# Schematic_v2.net
KiCad netlist of a schematic drawn in EAGLE
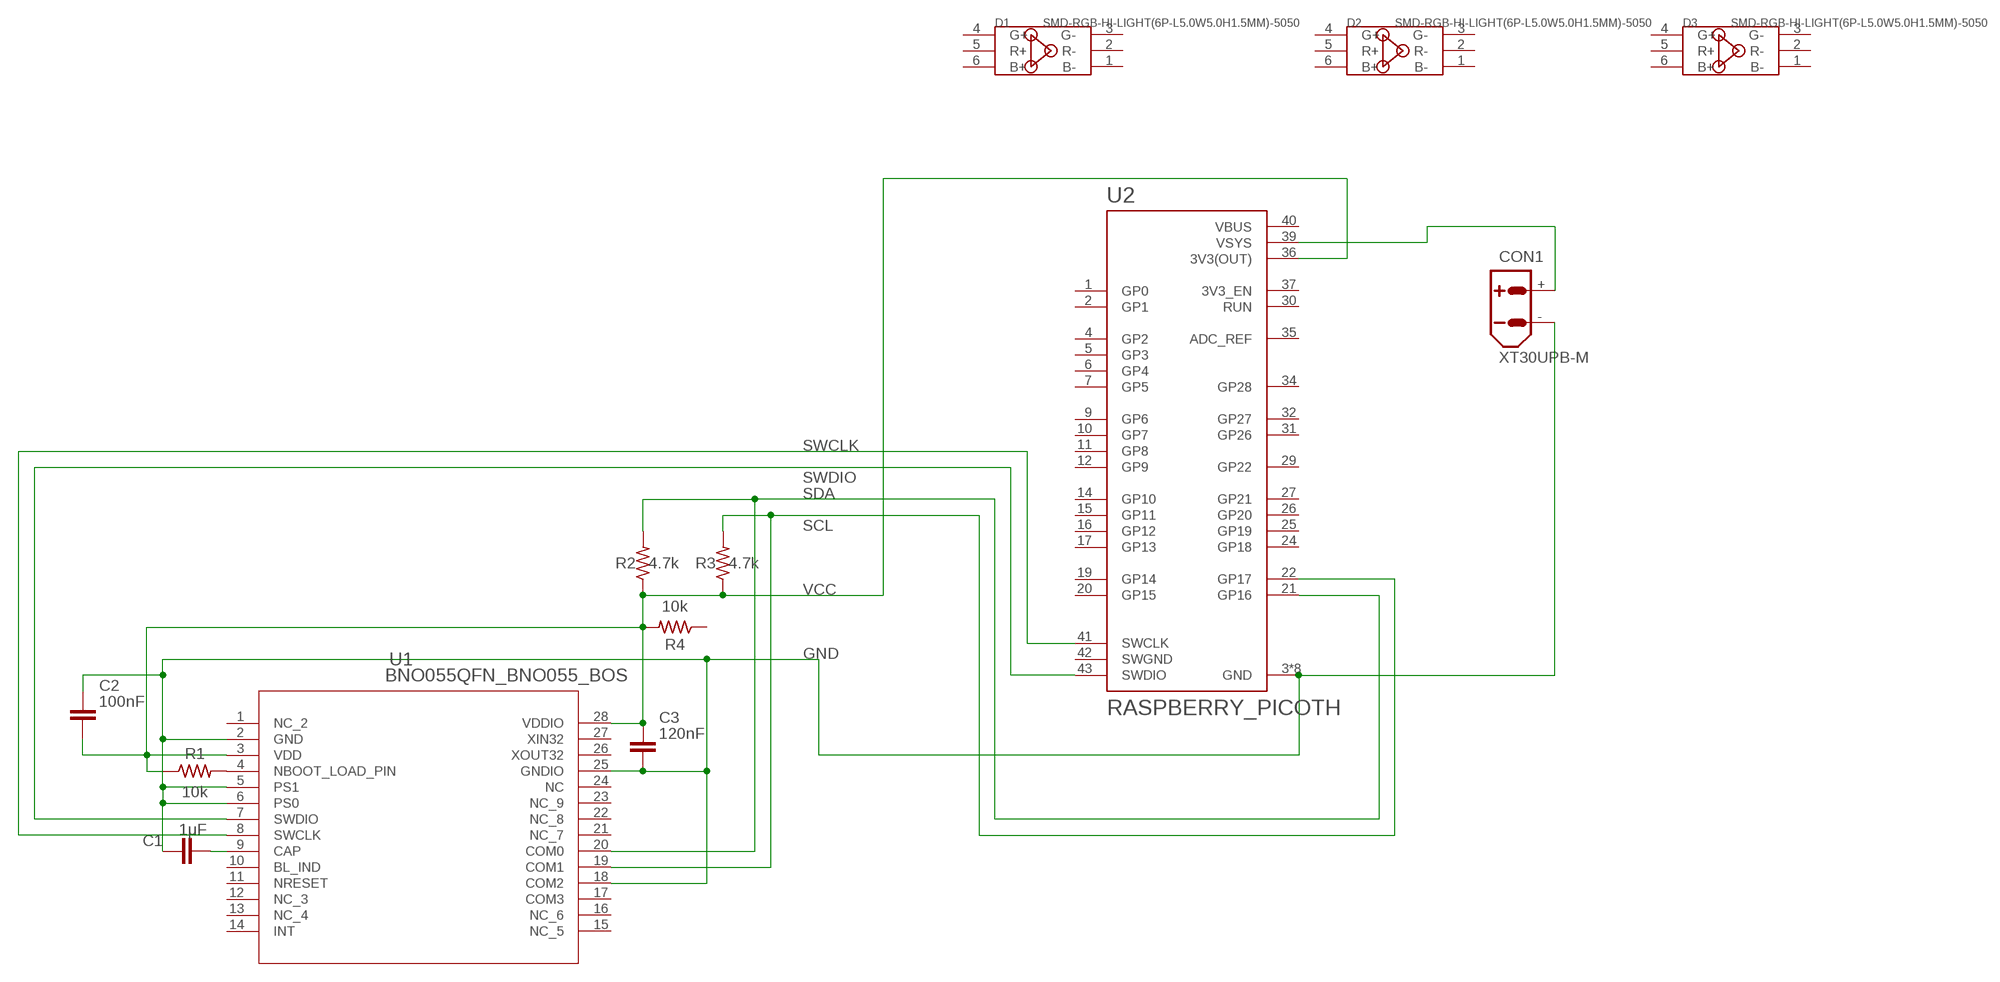
[diagram p0: schematic, sheet 1]

(export (version "E")
  (design (tool "Eeschema 10.0.6"))
  (components
    (comp (ref "C1")
      (value "1μF")
      (footprint "eagle-import:CAPC3216X135")
      (libsource (lib "eagle-import") (part "CCHIP-1206(3216-METRIC)_"))
    )
    (comp (ref "C2")
      (value "100nF")
      (footprint "eagle-import:CAPC3216X135")
      (libsource (lib "eagle-import") (part "CCHIP-1206(3216-METRIC)_"))
    )
    (comp (ref "C3")
      (value "120nF")
      (footprint "eagle-import:CAPC3216X135")
      (libsource (lib "eagle-import") (part "CCHIP-1206(3216-METRIC)_"))
    )
    (comp (ref "CON1")
      (value "XT30UPB-M")
      (footprint "eagle-import:XT30UPB-M")
      (libsource (lib "eagle-import") (part "XT30UPB-M"))
    )
    (comp (ref "D1")
      (value "SMD-RGB-HI-LIGHT(6P-L5.0W5.0H1.5MM)-5050")
      (footprint "eagle-import:LED6-SMD-5050")
      (fields (field (name "MF") "SparkFun Electronics") (field (name "MP") "5050RGB"))
      (libsource (lib "eagle-import") (part "SMD-RGB-HI-LIGHT(6P-L5.0W5.0H1.5MM)-5050"))
    )
    (comp (ref "D2")
      (value "SMD-RGB-HI-LIGHT(6P-L5.0W5.0H1.5MM)-5050")
      (footprint "eagle-import:LED6-SMD-5050")
      (fields (field (name "MF") "SparkFun Electronics") (field (name "MP") "5050RGB"))
      (libsource (lib "eagle-import") (part "SMD-RGB-HI-LIGHT(6P-L5.0W5.0H1.5MM)-5050"))
    )
    (comp (ref "D3")
      (value "SMD-RGB-HI-LIGHT(6P-L5.0W5.0H1.5MM)-5050")
      (footprint "eagle-import:LED6-SMD-5050")
      (fields (field (name "MF") "SparkFun Electronics") (field (name "MP") "5050RGB"))
      (libsource (lib "eagle-import") (part "SMD-RGB-HI-LIGHT(6P-L5.0W5.0H1.5MM)-5050"))
    )
    (comp (ref "R1")
      (value "10k")
      (footprint "eagle-import:RESC3216X70")
      (libsource (lib "eagle-import") (part "R-USCHIP-1206(3216-METRIC)_"))
    )
    (comp (ref "R2")
      (value "4.7k")
      (footprint "eagle-import:RESC3216X70")
      (libsource (lib "eagle-import") (part "R-USCHIP-1206(3216-METRIC)_"))
    )
    (comp (ref "R3")
      (value "4.7k")
      (footprint "eagle-import:RESC3216X70")
      (libsource (lib "eagle-import") (part "R-USCHIP-1206(3216-METRIC)_"))
    )
    (comp (ref "R4")
      (value "10k")
      (footprint "eagle-import:RESC3216X70")
      (libsource (lib "eagle-import") (part "R-USCHIP-1206(3216-METRIC)_"))
    )
    (comp (ref "U1")
      (value "BNO055QFN_BNO055_BOS")
      (footprint "eagle-import:QFN_BNO055_BOS")
      (fields
        (field (name "MANUFACTURER_PART_NUMBER") "BNO055")
        (field (name "COPYRIGHT") "Copyright (C) 2024 Ultra Librarian. All rights reserved.")
      )
      (libsource (lib "eagle-import") (part "BNO055QFN_BNO055_BOS"))
    )
    (comp (ref "U2")
      (value "RASPBERRY_PICOTH")
      (footprint "eagle-import:PICO-PKG-TH")
      (libsource (lib "eagle-import") (part "RASPBERRY_PICOTH"))
    )
  )
  (nets
    (net (code "1") (name "/GND") (class "Default")
      (node (ref "C1") (pin "1") (pinfunction "1_1") (pintype "passive"))
      (node (ref "C2") (pin "1") (pinfunction "1_1") (pintype "passive"))
      (node (ref "C3") (pin "2") (pinfunction "2_2") (pintype "passive"))
      (node (ref "CON1") (pin "-") (pinfunction "-_-") (pintype "power_in"))
      (node (ref "U1") (pin "18") (pinfunction "COM2_18") (pintype "bidirectional"))
      (node (ref "U1") (pin "2") (pinfunction "GND_2") (pintype "passive"))
      (node (ref "U1") (pin "25") (pinfunction "GNDIO_25") (pintype "passive"))
      (node (ref "U1") (pin "5") (pinfunction "PS1_5") (pintype "input"))
      (node (ref "U1") (pin "6") (pinfunction "PS0_6") (pintype "input"))
      (node (ref "U2") (pin "13") (pinfunction "GND_13") (pintype "power_in"))
      (node (ref "U2") (pin "18") (pinfunction "GND_18") (pintype "power_in"))
      (node (ref "U2") (pin "23") (pinfunction "GND_23") (pintype "power_in"))
      (node (ref "U2") (pin "28") (pinfunction "GND_28") (pintype "power_in"))
      (node (ref "U2") (pin "3") (pinfunction "GND_3") (pintype "power_in"))
      (node (ref "U2") (pin "33") (pinfunction "GND_33") (pintype "power_in"))
      (node (ref "U2") (pin "38") (pinfunction "GND_38") (pintype "power_in"))
      (node (ref "U2") (pin "8") (pinfunction "GND_8") (pintype "power_in"))
    )
    (net (code "2") (name "/SCL") (class "Default")
      (node (ref "R3") (pin "2") (pinfunction "2_2") (pintype "passive"))
      (node (ref "U1") (pin "19") (pinfunction "COM1_19") (pintype "bidirectional"))
      (node (ref "U2") (pin "22") (pinfunction "GP17_22") (pintype "bidirectional"))
    )
    (net (code "3") (name "/SDA") (class "Default")
      (node (ref "R2") (pin "2") (pinfunction "2_2") (pintype "passive"))
      (node (ref "U1") (pin "20") (pinfunction "COM0_20") (pintype "bidirectional"))
      (node (ref "U2") (pin "21") (pinfunction "GP16_21") (pintype "bidirectional"))
    )
    (net (code "4") (name "/SWCLK") (class "Default")
      (node (ref "U1") (pin "8") (pinfunction "SWCLK_8") (pintype "input"))
      (node (ref "U2") (pin "41") (pinfunction "SWCLK_41") (pintype "input"))
    )
    (net (code "5") (name "/SWDIO") (class "Default")
      (node (ref "U1") (pin "7") (pinfunction "SWDIO_7") (pintype "bidirectional"))
      (node (ref "U2") (pin "43") (pinfunction "SWDIO_43") (pintype "bidirectional"))
    )
    (net (code "6") (name "/SWGND") (class "Default")
      (node (ref "U2") (pin "42") (pinfunction "SWGND_42") (pintype "power_in"))
    )
    (net (code "7") (name "/VBUS") (class "Default")
      (node (ref "U2") (pin "40") (pinfunction "VBUS_40") (pintype "power_in"))
    )
    (net (code "8") (name "/VCC") (class "Default")
      (node (ref "C2") (pin "2") (pinfunction "2_2") (pintype "passive"))
      (node (ref "C3") (pin "1") (pinfunction "1_1") (pintype "passive"))
      (node (ref "R1") (pin "1") (pinfunction "1_1") (pintype "passive"))
      (node (ref "R2") (pin "1") (pinfunction "1_1") (pintype "passive"))
      (node (ref "R3") (pin "1") (pinfunction "1_1") (pintype "passive"))
      (node (ref "R4") (pin "2") (pinfunction "2_2") (pintype "passive"))
      (node (ref "U1") (pin "28") (pinfunction "VDDIO_28") (pintype "power_in"))
      (node (ref "U1") (pin "3") (pinfunction "VDD_3") (pintype "power_in"))
      (node (ref "U2") (pin "36") (pinfunction "3V3(OUT)_36") (pintype "power_in"))
    )
    (net (code "9") (name "Net-(U1-CAP)") (class "Default")
      (node (ref "C1") (pin "2") (pinfunction "2_2") (pintype "passive"))
      (node (ref "U1") (pin "9") (pinfunction "CAP_9") (pintype "passive"))
    )
    (net (code "10") (name "Net-(U1-NBOOT_LOAD_PIN)") (class "Default")
      (node (ref "R1") (pin "2") (pinfunction "2_2") (pintype "passive"))
      (node (ref "U1") (pin "4") (pinfunction "NBOOT_LOAD_PIN_4") (pintype "input"))
    )
    (net (code "11") (name "Net-(U2-VSYS)") (class "Default")
      (node (ref "CON1") (pin "+") (pinfunction "+_+") (pintype "power_in"))
      (node (ref "U2") (pin "39") (pinfunction "VSYS_39") (pintype "power_in"))
    )
    (net (code "12") (name "unconnected-(D1-B+-Pad6)") (class "Default")
      (node (ref "D1") (pin "6") (pinfunction "B+_6") (pintype "bidirectional"))
    )
    (net (code "13") (name "unconnected-(D1-B--Pad1)") (class "Default")
      (node (ref "D1") (pin "1") (pinfunction "B-_1") (pintype "bidirectional"))
    )
    (net (code "14") (name "unconnected-(D1-G+-Pad4)") (class "Default")
      (node (ref "D1") (pin "4") (pinfunction "G+_4") (pintype "bidirectional"))
    )
    (net (code "15") (name "unconnected-(D1-G--Pad3)") (class "Default")
      (node (ref "D1") (pin "3") (pinfunction "G-_3") (pintype "bidirectional"))
    )
    (net (code "16") (name "unconnected-(D1-R+-Pad5)") (class "Default")
      (node (ref "D1") (pin "5") (pinfunction "R+_5") (pintype "bidirectional"))
    )
    (net (code "17") (name "unconnected-(D1-R--Pad2)") (class "Default")
      (node (ref "D1") (pin "2") (pinfunction "R-_2") (pintype "bidirectional"))
    )
    (net (code "18") (name "unconnected-(D2-B+-Pad6)") (class "Default")
      (node (ref "D2") (pin "6") (pinfunction "B+_6") (pintype "bidirectional"))
    )
    (net (code "19") (name "unconnected-(D2-B--Pad1)") (class "Default")
      (node (ref "D2") (pin "1") (pinfunction "B-_1") (pintype "bidirectional"))
    )
    (net (code "20") (name "unconnected-(D2-G+-Pad4)") (class "Default")
      (node (ref "D2") (pin "4") (pinfunction "G+_4") (pintype "bidirectional"))
    )
    (net (code "21") (name "unconnected-(D2-G--Pad3)") (class "Default")
      (node (ref "D2") (pin "3") (pinfunction "G-_3") (pintype "bidirectional"))
    )
    (net (code "22") (name "unconnected-(D2-R+-Pad5)") (class "Default")
      (node (ref "D2") (pin "5") (pinfunction "R+_5") (pintype "bidirectional"))
    )
    (net (code "23") (name "unconnected-(D2-R--Pad2)") (class "Default")
      (node (ref "D2") (pin "2") (pinfunction "R-_2") (pintype "bidirectional"))
    )
    (net (code "24") (name "unconnected-(D3-B+-Pad6)") (class "Default")
      (node (ref "D3") (pin "6") (pinfunction "B+_6") (pintype "bidirectional"))
    )
    (net (code "25") (name "unconnected-(D3-B--Pad1)") (class "Default")
      (node (ref "D3") (pin "1") (pinfunction "B-_1") (pintype "bidirectional"))
    )
    (net (code "26") (name "unconnected-(D3-G+-Pad4)") (class "Default")
      (node (ref "D3") (pin "4") (pinfunction "G+_4") (pintype "bidirectional"))
    )
    (net (code "27") (name "unconnected-(D3-G--Pad3)") (class "Default")
      (node (ref "D3") (pin "3") (pinfunction "G-_3") (pintype "bidirectional"))
    )
    (net (code "28") (name "unconnected-(D3-R+-Pad5)") (class "Default")
      (node (ref "D3") (pin "5") (pinfunction "R+_5") (pintype "bidirectional"))
    )
    (net (code "29") (name "unconnected-(D3-R--Pad2)") (class "Default")
      (node (ref "D3") (pin "2") (pinfunction "R-_2") (pintype "bidirectional"))
    )
    (net (code "30") (name "unconnected-(R4-Pad1)") (class "Default")
      (node (ref "R4") (pin "1") (pinfunction "1_1") (pintype "passive"))
    )
    (net (code "31") (name "unconnected-(U1-BL_IND-Pad10)") (class "Default")
      (node (ref "U1") (pin "10") (pinfunction "BL_IND_10") (pintype "output"))
    )
    (net (code "32") (name "unconnected-(U1-COM3-Pad17)") (class "Default")
      (node (ref "U1") (pin "17") (pinfunction "COM3_17") (pintype "input"))
    )
    (net (code "33") (name "unconnected-(U1-INT-Pad14)") (class "Default")
      (node (ref "U1") (pin "14") (pinfunction "INT_14") (pintype "output"))
    )
    (net (code "34") (name "unconnected-(U1-NC-Pad24)") (class "Default")
      (node (ref "U1") (pin "24") (pinfunction "NC_24") (pintype "no_connect"))
    )
    (net (code "35") (name "unconnected-(U1-NC_2-Pad1)") (class "Default")
      (node (ref "U1") (pin "1") (pinfunction "NC_2_1") (pintype "no_connect"))
    )
    (net (code "36") (name "unconnected-(U1-NC_3-Pad12)") (class "Default")
      (node (ref "U1") (pin "12") (pinfunction "NC_3_12") (pintype "no_connect"))
    )
    (net (code "37") (name "unconnected-(U1-NC_4-Pad13)") (class "Default")
      (node (ref "U1") (pin "13") (pinfunction "NC_4_13") (pintype "no_connect"))
    )
    (net (code "38") (name "unconnected-(U1-NC_5-Pad15)") (class "Default")
      (node (ref "U1") (pin "15") (pinfunction "NC_5_15") (pintype "no_connect"))
    )
    (net (code "39") (name "unconnected-(U1-NC_6-Pad16)") (class "Default")
      (node (ref "U1") (pin "16") (pinfunction "NC_6_16") (pintype "no_connect"))
    )
    (net (code "40") (name "unconnected-(U1-NC_7-Pad21)") (class "Default")
      (node (ref "U1") (pin "21") (pinfunction "NC_7_21") (pintype "no_connect"))
    )
    (net (code "41") (name "unconnected-(U1-NC_8-Pad22)") (class "Default")
      (node (ref "U1") (pin "22") (pinfunction "NC_8_22") (pintype "no_connect"))
    )
    (net (code "42") (name "unconnected-(U1-NC_9-Pad23)") (class "Default")
      (node (ref "U1") (pin "23") (pinfunction "NC_9_23") (pintype "no_connect"))
    )
    (net (code "43") (name "unconnected-(U1-NRESET-Pad11)") (class "Default")
      (node (ref "U1") (pin "11") (pinfunction "NRESET_11") (pintype "passive"))
    )
    (net (code "44") (name "unconnected-(U1-XIN32-Pad27)") (class "Default")
      (node (ref "U1") (pin "27") (pinfunction "XIN32_27") (pintype "input"))
    )
    (net (code "45") (name "unconnected-(U1-XOUT32-Pad26)") (class "Default")
      (node (ref "U1") (pin "26") (pinfunction "XOUT32_26") (pintype "output"))
    )
    (net (code "46") (name "unconnected-(U2-3V3_EN-Pad37)") (class "Default")
      (node (ref "U2") (pin "37") (pinfunction "3V3_EN_37") (pintype "input"))
    )
    (net (code "47") (name "unconnected-(U2-ADC_REF-Pad35)") (class "Default")
      (node (ref "U2") (pin "35") (pinfunction "ADC_REF_35") (pintype "input"))
    )
    (net (code "48") (name "unconnected-(U2-GP0-Pad1)") (class "Default")
      (node (ref "U2") (pin "1") (pinfunction "GP0_1") (pintype "bidirectional"))
    )
    (net (code "49") (name "unconnected-(U2-GP1-Pad2)") (class "Default")
      (node (ref "U2") (pin "2") (pinfunction "GP1_2") (pintype "bidirectional"))
    )
    (net (code "50") (name "unconnected-(U2-GP2-Pad4)") (class "Default")
      (node (ref "U2") (pin "4") (pinfunction "GP2_4") (pintype "bidirectional"))
    )
    (net (code "51") (name "unconnected-(U2-GP3-Pad5)") (class "Default")
      (node (ref "U2") (pin "5") (pinfunction "GP3_5") (pintype "bidirectional"))
    )
    (net (code "52") (name "unconnected-(U2-GP4-Pad6)") (class "Default")
      (node (ref "U2") (pin "6") (pinfunction "GP4_6") (pintype "bidirectional"))
    )
    (net (code "53") (name "unconnected-(U2-GP5-Pad7)") (class "Default")
      (node (ref "U2") (pin "7") (pinfunction "GP5_7") (pintype "bidirectional"))
    )
    (net (code "54") (name "unconnected-(U2-GP6-Pad9)") (class "Default")
      (node (ref "U2") (pin "9") (pinfunction "GP6_9") (pintype "bidirectional"))
    )
    (net (code "55") (name "unconnected-(U2-GP7-Pad10)") (class "Default")
      (node (ref "U2") (pin "10") (pinfunction "GP7_10") (pintype "bidirectional"))
    )
    (net (code "56") (name "unconnected-(U2-GP8-Pad11)") (class "Default")
      (node (ref "U2") (pin "11") (pinfunction "GP8_11") (pintype "bidirectional"))
    )
    (net (code "57") (name "unconnected-(U2-GP9-Pad12)") (class "Default")
      (node (ref "U2") (pin "12") (pinfunction "GP9_12") (pintype "bidirectional"))
    )
    (net (code "58") (name "unconnected-(U2-GP10-Pad14)") (class "Default")
      (node (ref "U2") (pin "14") (pinfunction "GP10_14") (pintype "bidirectional"))
    )
    (net (code "59") (name "unconnected-(U2-GP11-Pad15)") (class "Default")
      (node (ref "U2") (pin "15") (pinfunction "GP11_15") (pintype "bidirectional"))
    )
    (net (code "60") (name "unconnected-(U2-GP12-Pad16)") (class "Default")
      (node (ref "U2") (pin "16") (pinfunction "GP12_16") (pintype "bidirectional"))
    )
    (net (code "61") (name "unconnected-(U2-GP13-Pad17)") (class "Default")
      (node (ref "U2") (pin "17") (pinfunction "GP13_17") (pintype "bidirectional"))
    )
    (net (code "62") (name "unconnected-(U2-GP14-Pad19)") (class "Default")
      (node (ref "U2") (pin "19") (pinfunction "GP14_19") (pintype "bidirectional"))
    )
    (net (code "63") (name "unconnected-(U2-GP15-Pad20)") (class "Default")
      (node (ref "U2") (pin "20") (pinfunction "GP15_20") (pintype "bidirectional"))
    )
    (net (code "64") (name "unconnected-(U2-GP18-Pad24)") (class "Default")
      (node (ref "U2") (pin "24") (pinfunction "GP18_24") (pintype "bidirectional"))
    )
    (net (code "65") (name "unconnected-(U2-GP19-Pad25)") (class "Default")
      (node (ref "U2") (pin "25") (pinfunction "GP19_25") (pintype "bidirectional"))
    )
    (net (code "66") (name "unconnected-(U2-GP20-Pad26)") (class "Default")
      (node (ref "U2") (pin "26") (pinfunction "GP20_26") (pintype "bidirectional"))
    )
    (net (code "67") (name "unconnected-(U2-GP21-Pad27)") (class "Default")
      (node (ref "U2") (pin "27") (pinfunction "GP21_27") (pintype "bidirectional"))
    )
    (net (code "68") (name "unconnected-(U2-GP22-Pad29)") (class "Default")
      (node (ref "U2") (pin "29") (pinfunction "GP22_29") (pintype "bidirectional"))
    )
    (net (code "69") (name "unconnected-(U2-GP26-Pad31)") (class "Default")
      (node (ref "U2") (pin "31") (pinfunction "GP26_31") (pintype "bidirectional"))
    )
    (net (code "70") (name "unconnected-(U2-GP27-Pad32)") (class "Default")
      (node (ref "U2") (pin "32") (pinfunction "GP27_32") (pintype "bidirectional"))
    )
    (net (code "71") (name "unconnected-(U2-GP28-Pad34)") (class "Default")
      (node (ref "U2") (pin "34") (pinfunction "GP28_34") (pintype "bidirectional"))
    )
    (net (code "72") (name "unconnected-(U2-RUN-Pad30)") (class "Default")
      (node (ref "U2") (pin "30") (pinfunction "RUN_30") (pintype "input"))
    )
  )
)
